# Conn_pcb4.net
KiCad netlist of a schematic drawn in EAGLE
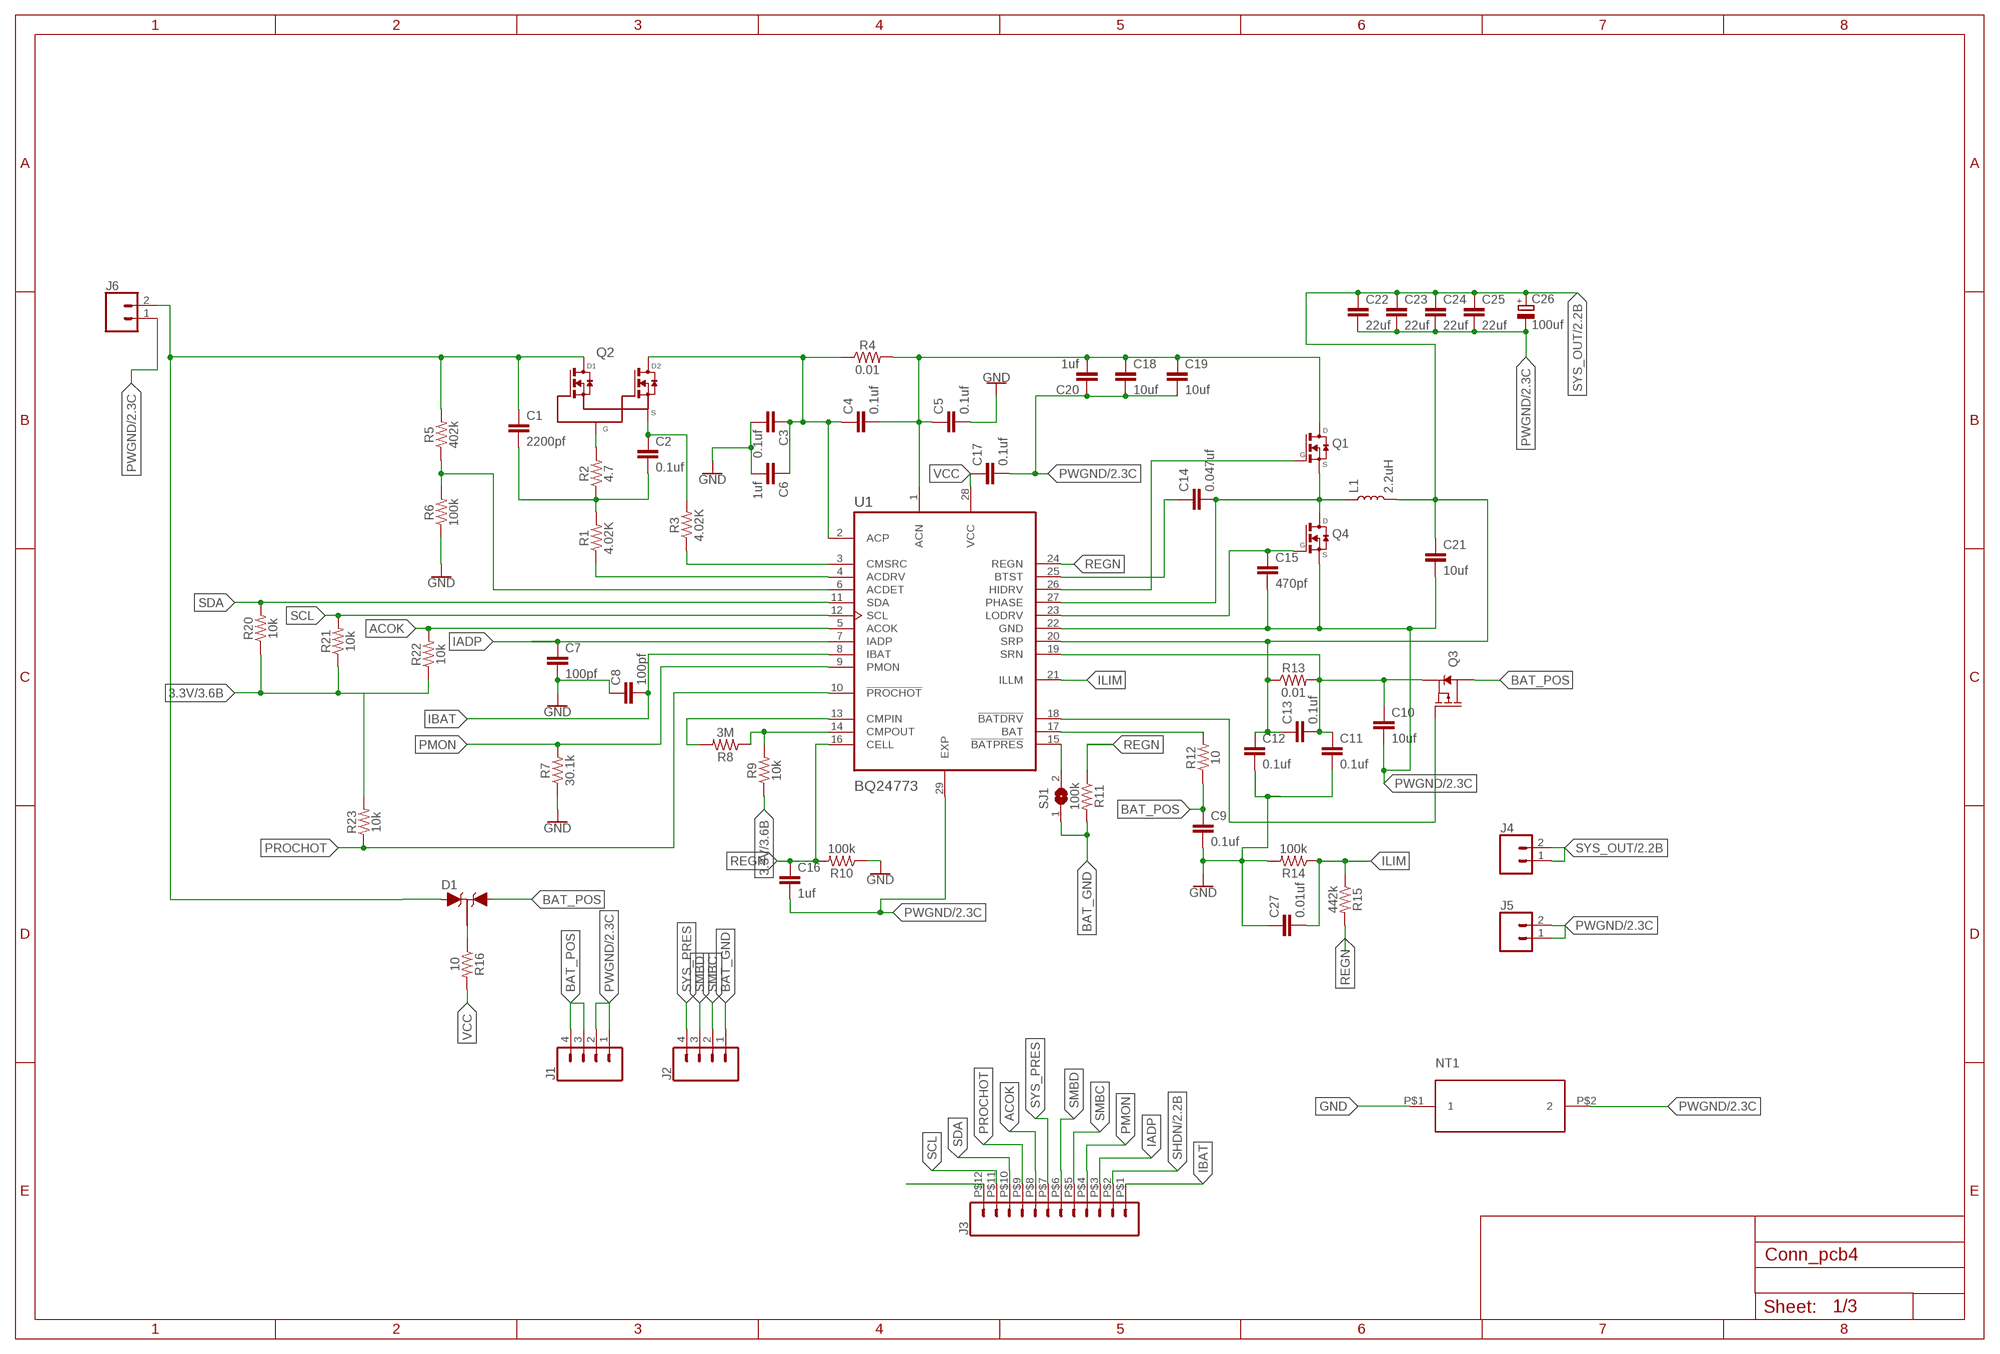
[diagram p0: schematic, sheet 1]
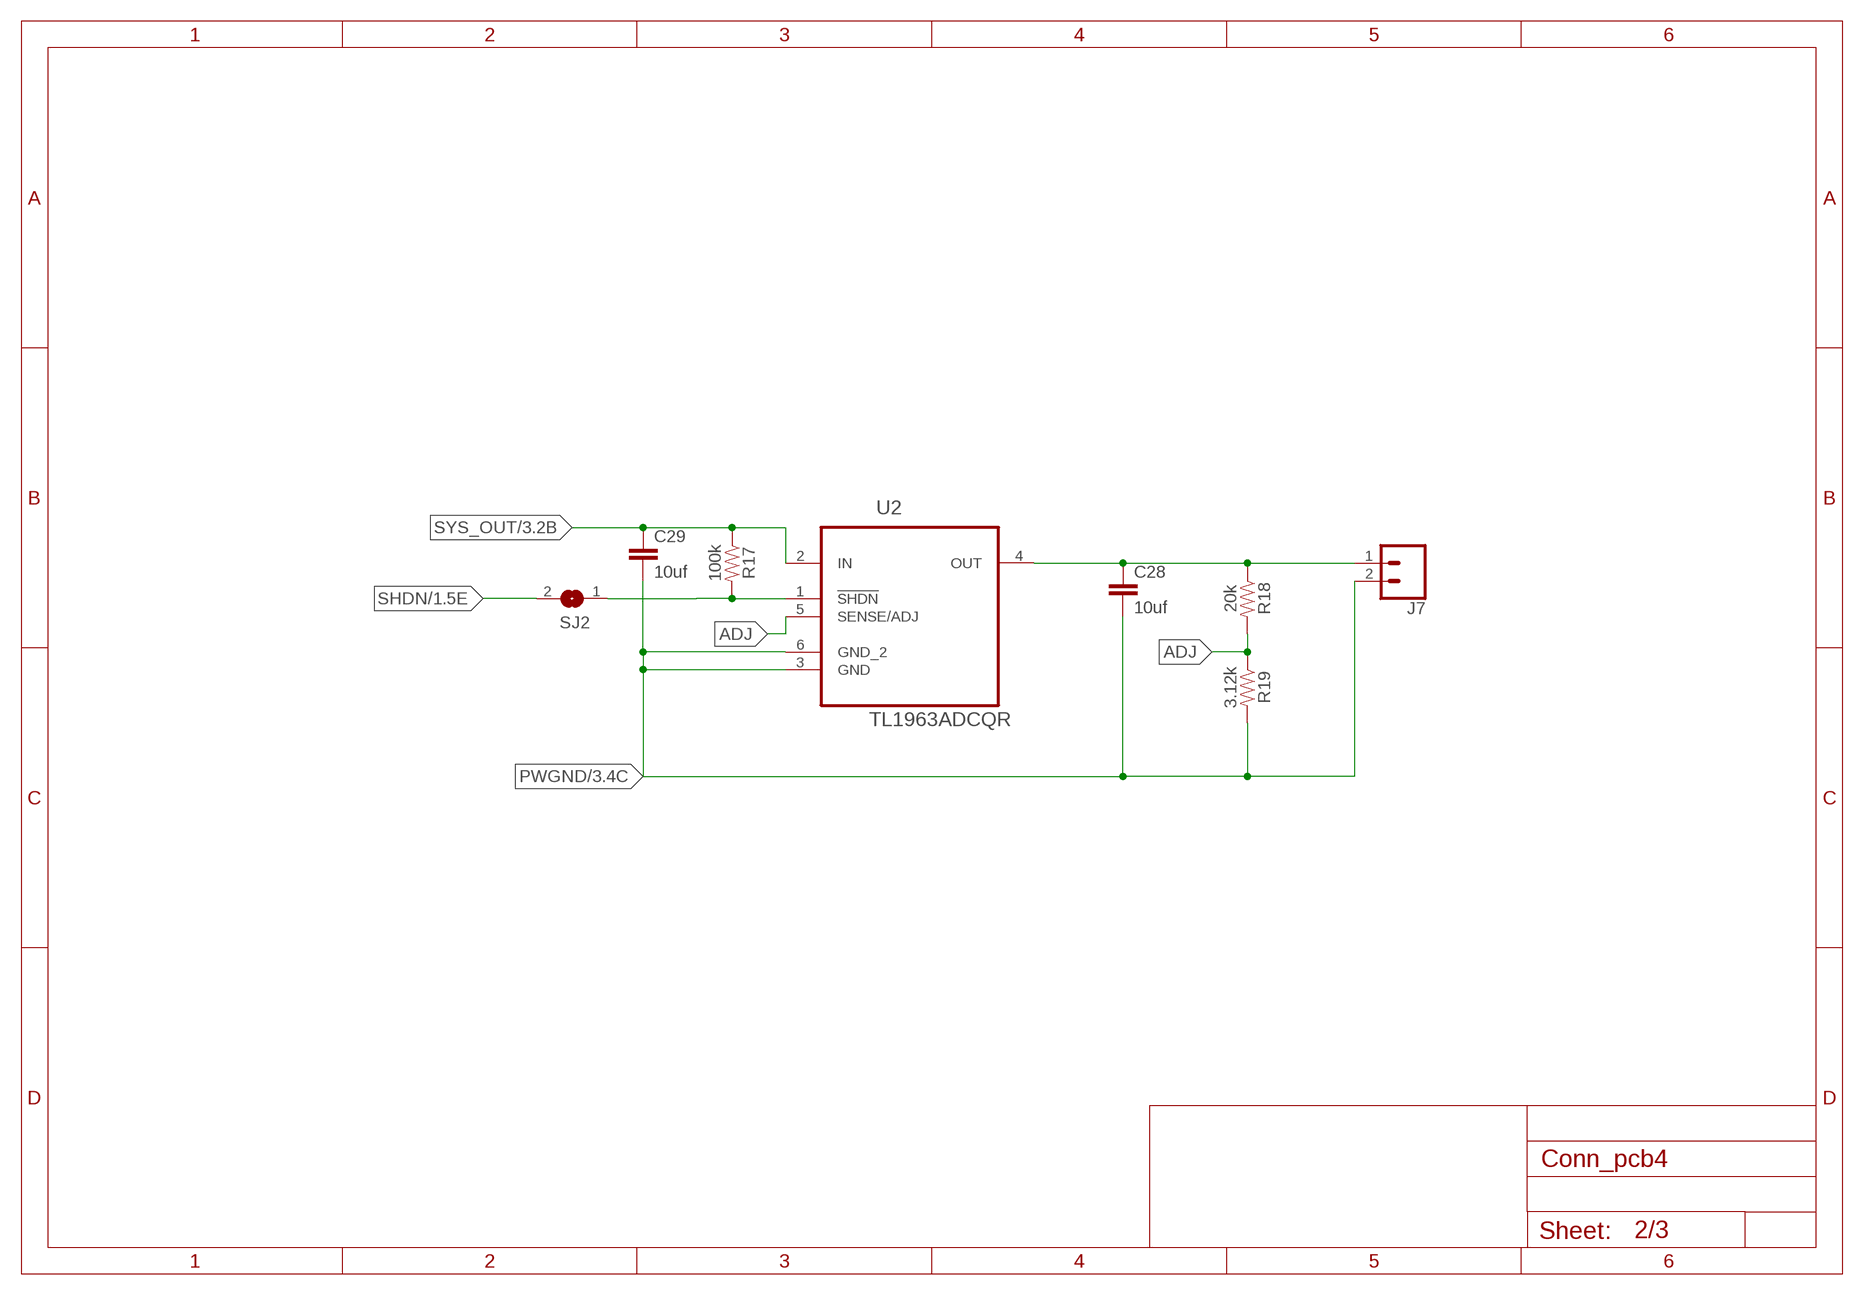
[diagram p1: schematic, sheet 2]
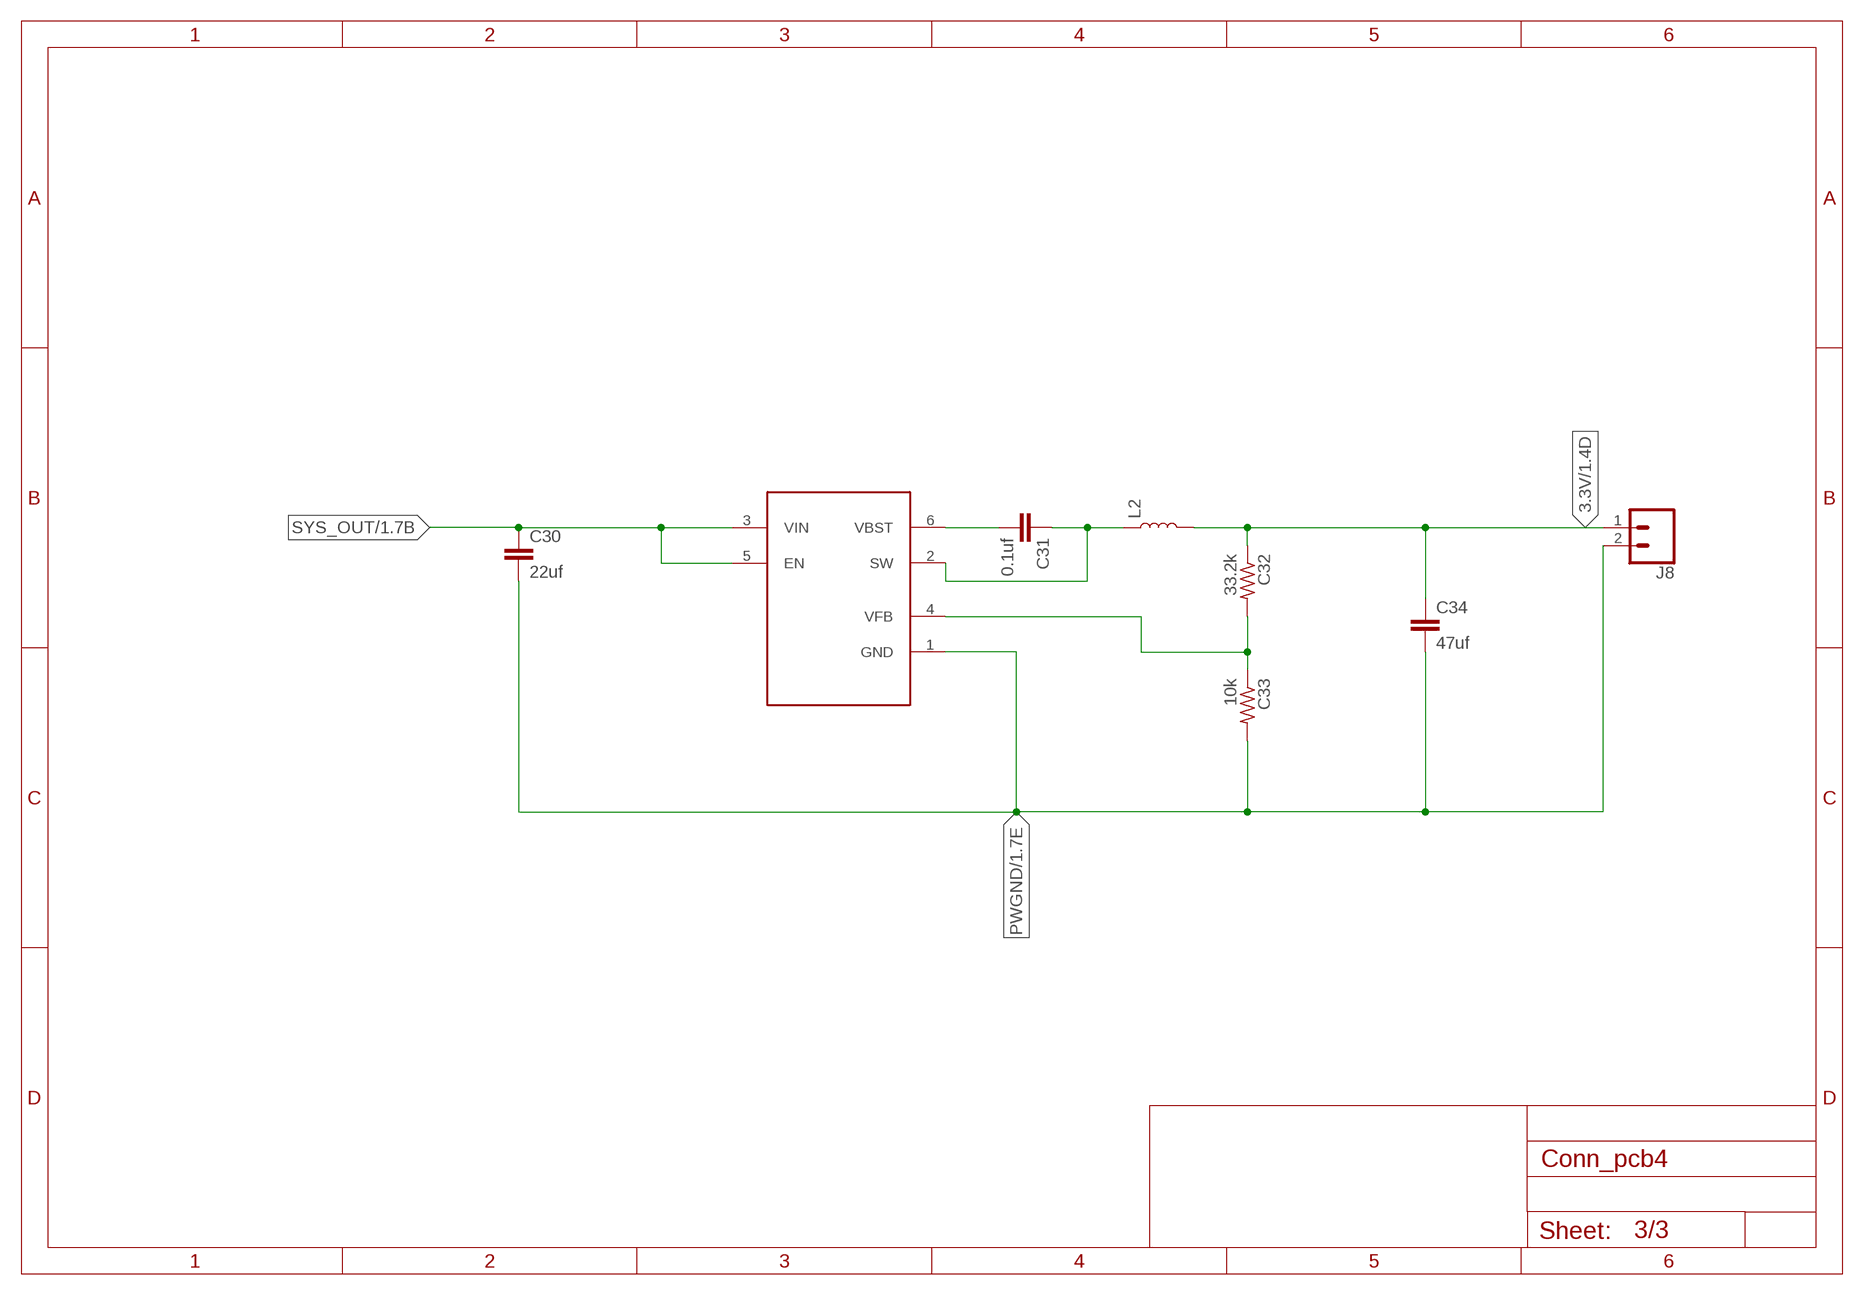
[diagram p2: schematic, sheet 3]

(export (version "E")
  (design (tool "Eeschema 10.0.6"))
  (components
    (comp (ref "C28")
      (value "10uf")
      (footprint "eagle-import:C0805K")
      (libsource (lib "eagle-import") (part "C-EUC0805K"))
    )
    (comp (ref "C29")
      (value "10uf")
      (footprint "eagle-import:C0805K")
      (libsource (lib "eagle-import") (part "C-EUC0805K"))
    )
    (comp (ref "J7")
      (value "CONN_02")
      (footprint "eagle-import:1X02")
      (libsource (lib "eagle-import") (part "CONN_02"))
    )
    (comp (ref "R17")
      (value "100k")
      (footprint "eagle-import:0402")
      (libsource (lib "eagle-import") (part "RES4K04020402"))
    )
    (comp (ref "R18")
      (value "20k")
      (footprint "eagle-import:0402")
      (libsource (lib "eagle-import") (part "RES4K04020402"))
    )
    (comp (ref "R19")
      (value "3.12k")
      (footprint "eagle-import:0402")
      (libsource (lib "eagle-import") (part "RES4K04020402"))
    )
    (comp (ref "SJ2") (value "SJ") (footprint "eagle-import:SJ") (libsource (lib "eagle-import") (part "SJ")))
    (comp (ref "U2")
      (value "TL1963ADCQR")
      (footprint "eagle-import:SOT127P706X180-6")
      (libsource (lib "eagle-import") (part "TL1963ADCQR"))
    )
    (comp (ref "C30")
      (value "22uf")
      (footprint "eagle-import:C1206")
      (libsource (lib "eagle-import") (part "C-EUC1206"))
    )
    (comp (ref "C31")
      (value "0.1uf")
      (footprint "eagle-import:CAPC1005X50")
      (libsource (lib "eagle-import") (part "CAP0402"))
    )
    (comp (ref "C32")
      (value "33.2k")
      (footprint "eagle-import:R0805")
      (libsource (lib "eagle-import") (part "R-US_R0805"))
    )
    (comp (ref "C33")
      (value "10k")
      (footprint "eagle-import:R0603")
      (libsource (lib "eagle-import") (part "R-US_R0603"))
    )
    (comp (ref "C34")
      (value "47uf")
      (footprint "eagle-import:C1206K")
      (libsource (lib "eagle-import") (part "C-EUC1206K"))
    )
    (comp (ref "J8")
      (value "CONN_02")
      (footprint "eagle-import:1X02")
      (libsource (lib "eagle-import") (part "CONN_02"))
    )
    (comp (ref "L2")
      (value "ASPI-4030S-3R3M-T")
      (footprint "eagle-import:INDDFN400X400X300-2")
      (libsource (lib "eagle-import") (part "ASPI-4030S-3R3M-T"))
    )
    (comp (ref "U3")
      (value "TPS561208DDCR")
      (footprint "eagle-import:SOT95P280X110-6")
      (libsource (lib "eagle-import") (part "TPS561208DDCR"))
    )
    (comp (ref "C1")
      (value "2200pf")
      (footprint "eagle-import:CAPC1005X50")
      (libsource (lib "eagle-import") (part "CAP0402"))
    )
    (comp (ref "C2")
      (value "0.1uf")
      (footprint "eagle-import:CAPC1005X50")
      (libsource (lib "eagle-import") (part "CAP0402"))
    )
    (comp (ref "C3")
      (value "0.1uf")
      (footprint "eagle-import:CAPC1005X50")
      (libsource (lib "eagle-import") (part "CAP0402"))
    )
    (comp (ref "C4")
      (value "0.1uf")
      (footprint "eagle-import:CAPC1005X50")
      (libsource (lib "eagle-import") (part "CAP0402"))
    )
    (comp (ref "C5")
      (value "0.1uf")
      (footprint "eagle-import:CAPC1005X50")
      (libsource (lib "eagle-import") (part "CAP0402"))
    )
    (comp (ref "C6")
      (value "1uf")
      (footprint "eagle-import:CAPC1005X50")
      (libsource (lib "eagle-import") (part "CAP0402"))
    )
    (comp (ref "C7")
      (value "100pf")
      (footprint "eagle-import:CAPC1005X50")
      (libsource (lib "eagle-import") (part "CAP0402"))
    )
    (comp (ref "C8")
      (value "100pf")
      (footprint "eagle-import:CAPC1005X50")
      (libsource (lib "eagle-import") (part "CAP0402"))
    )
    (comp (ref "C9")
      (value "0.1uf")
      (footprint "eagle-import:CAPC1005X50")
      (libsource (lib "eagle-import") (part "CAP0402"))
    )
    (comp (ref "C10")
      (value "10uf")
      (footprint "eagle-import:C0805K")
      (libsource (lib "eagle-import") (part "C-EUC0805K"))
    )
    (comp (ref "C11")
      (value "0.1uf")
      (footprint "eagle-import:CAPC1005X50")
      (libsource (lib "eagle-import") (part "CAP0402"))
    )
    (comp (ref "C12")
      (value "0.1uf")
      (footprint "eagle-import:CAPC1005X50")
      (libsource (lib "eagle-import") (part "CAP0402"))
    )
    (comp (ref "C13")
      (value "0.1uf")
      (footprint "eagle-import:CAPC1005X50")
      (libsource (lib "eagle-import") (part "CAP0402"))
    )
    (comp (ref "C14")
      (value "0.047uf")
      (footprint "eagle-import:CAPC1005X50")
      (libsource (lib "eagle-import") (part "CAP0402"))
    )
    (comp (ref "C15")
      (value "470pf")
      (footprint "eagle-import:CAPC1005X50")
      (libsource (lib "eagle-import") (part "CAP0402"))
    )
    (comp (ref "C16")
      (value "1uf")
      (footprint "eagle-import:CAPC1005X50")
      (libsource (lib "eagle-import") (part "CAP0402"))
    )
    (comp (ref "C17")
      (value "0.1uf")
      (footprint "eagle-import:CAPC1005X50")
      (libsource (lib "eagle-import") (part "CAP0402"))
    )
    (comp (ref "C18")
      (value "10uf")
      (footprint "eagle-import:C0805K")
      (libsource (lib "eagle-import") (part "C-EUC0805K"))
    )
    (comp (ref "C19")
      (value "10uf")
      (footprint "eagle-import:C0805K")
      (libsource (lib "eagle-import") (part "C-EUC0805K"))
    )
    (comp (ref "C20")
      (value "1uf")
      (footprint "eagle-import:CAPC1005X50")
      (libsource (lib "eagle-import") (part "CAP0402"))
    )
    (comp (ref "C21")
      (value "10uf")
      (footprint "eagle-import:C0805K")
      (libsource (lib "eagle-import") (part "C-EUC0805K"))
    )
    (comp (ref "C22")
      (value "22uf")
      (footprint "eagle-import:C1206")
      (libsource (lib "eagle-import") (part "C-EUC1206"))
    )
    (comp (ref "C23")
      (value "22uf")
      (footprint "eagle-import:C1206")
      (libsource (lib "eagle-import") (part "C-EUC1206"))
    )
    (comp (ref "C24")
      (value "22uf")
      (footprint "eagle-import:C1206")
      (libsource (lib "eagle-import") (part "C-EUC1206"))
    )
    (comp (ref "C25")
      (value "22uf")
      (footprint "eagle-import:C1206")
      (libsource (lib "eagle-import") (part "C-EUC1206"))
    )
    (comp (ref "C26")
      (value "100uf")
      (footprint "eagle-import:CAPAE1030X800")
      (libsource (lib "eagle-import") (part "16SVP100M"))
    )
    (comp (ref "C27")
      (value "0.01uf")
      (footprint "eagle-import:CAPC1005X50")
      (libsource (lib "eagle-import") (part "CAP0402"))
    )
    (comp (ref "D1")
      (value "BAT54C-7-F")
      (footprint "eagle-import:SOT95P235X110-3")
      (libsource (lib "eagle-import") (part "BAT54C-7-F"))
    )
    (comp (ref "J1")
      (value "CONN_041.3")
      (footprint "eagle-import:1X04_NO_SILK_1.3")
      (libsource (lib "eagle-import") (part "CONN_041.3"))
    )
    (comp (ref "J2")
      (value "CONN_041.3")
      (footprint "eagle-import:1X04_NO_SILK_1.3")
      (libsource (lib "eagle-import") (part "CONN_041.3"))
    )
    (comp (ref "J3")
      (value "62674-121121ALF")
      (footprint "eagle-import:62674-121121ALF")
      (libsource (lib "eagle-import") (part "62674-121121ALF"))
    )
    (comp (ref "J4")
      (value "CONN_021.4HOLE")
      (footprint "eagle-import:1X02_1.4HOLE")
      (libsource (lib "eagle-import") (part "CONN_021.4HOLE"))
    )
    (comp (ref "J5")
      (value "CONN_021.4HOLE")
      (footprint "eagle-import:1X02_1.4HOLE")
      (libsource (lib "eagle-import") (part "CONN_021.4HOLE"))
    )
    (comp (ref "J6")
      (value "CONN_021.4HOLE")
      (footprint "eagle-import:1X02_1.4HOLE")
      (libsource (lib "eagle-import") (part "CONN_021.4HOLE"))
    )
    (comp (ref "L1")
      (value "2.2uH")
      (footprint "eagle-import:RESM6365X610")
      (libsource (lib "eagle-import") (part "XEL6060-222MEB"))
    )
    (comp (ref "NT1")
      (value "NET_TIE")
      (footprint "eagle-import:NET_TIE")
      (libsource (lib "eagle-import") (part "NET_TIE"))
    )
    (comp (ref "Q1")
      (value "CSD17308Q3")
      (footprint "eagle-import:SON65P330X330X110-8")
      (fields (field (name "SPICEPREFIX") "Q"))
      (libsource (lib "eagle-import") (part "CSD17308Q3"))
    )
    (comp (ref "Q2")
      (value "CSD87312Q3EVSON")
      (footprint "eagle-import:QFN65P330X330X100-12")
      (libsource (lib "eagle-import") (part "CSD87312Q3EVSON"))
    )
    (comp (ref "Q3")
      (value "CSD25402Q3A")
      (footprint "eagle-import:CSD25402Q3A")
      (libsource (lib "eagle-import") (part "CSD25402Q3A"))
    )
    (comp (ref "Q4")
      (value "CSD17308Q3")
      (footprint "eagle-import:SON65P330X330X110-8")
      (fields (field (name "SPICEPREFIX") "Q"))
      (libsource (lib "eagle-import") (part "CSD17308Q3"))
    )
    (comp (ref "R1")
      (value "4.02K")
      (footprint "eagle-import:0402")
      (libsource (lib "eagle-import") (part "RES4K04020402"))
    )
    (comp (ref "R2")
      (value "4.7")
      (footprint "eagle-import:0402")
      (libsource (lib "eagle-import") (part "RES4K04020402"))
    )
    (comp (ref "R3")
      (value "4.02K")
      (footprint "eagle-import:0402")
      (libsource (lib "eagle-import") (part "RES4K04020402"))
    )
    (comp (ref "R4")
      (value "0.01")
      (footprint "eagle-import:1206")
      (libsource (lib "eagle-import") (part "SENSE-RES"))
    )
    (comp (ref "R5")
      (value "402k")
      (footprint "eagle-import:0402")
      (libsource (lib "eagle-import") (part "RES4K04020402"))
    )
    (comp (ref "R6")
      (value "100k")
      (footprint "eagle-import:0402")
      (libsource (lib "eagle-import") (part "RES4K04020402"))
    )
    (comp (ref "R7")
      (value "30.1k")
      (footprint "eagle-import:0402")
      (libsource (lib "eagle-import") (part "RES4K04020402"))
    )
    (comp (ref "R8")
      (value "3M")
      (footprint "eagle-import:0402")
      (libsource (lib "eagle-import") (part "RES4K04020402"))
    )
    (comp (ref "R9")
      (value "10k")
      (footprint "eagle-import:0402")
      (libsource (lib "eagle-import") (part "RES4K04020402"))
    )
    (comp (ref "R10")
      (value "100k")
      (footprint "eagle-import:0402")
      (libsource (lib "eagle-import") (part "RES4K04020402"))
    )
    (comp (ref "R11")
      (value "100k")
      (footprint "eagle-import:0402")
      (libsource (lib "eagle-import") (part "RES4K04020402"))
    )
    (comp (ref "R12")
      (value "10")
      (footprint "eagle-import:0402")
      (libsource (lib "eagle-import") (part "RES4K04020402"))
    )
    (comp (ref "R13")
      (value "0.01")
      (footprint "eagle-import:1206")
      (libsource (lib "eagle-import") (part "SENSE-RES"))
    )
    (comp (ref "R14")
      (value "100k")
      (footprint "eagle-import:0402")
      (libsource (lib "eagle-import") (part "RES4K04020402"))
    )
    (comp (ref "R15")
      (value "442k")
      (footprint "eagle-import:0402")
      (libsource (lib "eagle-import") (part "RES4K04020402"))
    )
    (comp (ref "R16")
      (value "10")
      (footprint "eagle-import:0402")
      (libsource (lib "eagle-import") (part "RES4K04020402"))
    )
    (comp (ref "R20")
      (value "10k")
      (footprint "eagle-import:0402")
      (libsource (lib "eagle-import") (part "RES4K04020402"))
    )
    (comp (ref "R21")
      (value "10k")
      (footprint "eagle-import:0402")
      (libsource (lib "eagle-import") (part "RES4K04020402"))
    )
    (comp (ref "R22")
      (value "10k")
      (footprint "eagle-import:0402")
      (libsource (lib "eagle-import") (part "RES4K04020402"))
    )
    (comp (ref "R23")
      (value "10k")
      (footprint "eagle-import:0402")
      (libsource (lib "eagle-import") (part "RES4K04020402"))
    )
    (comp (ref "SJ1") (value "SJ") (footprint "eagle-import:SJ") (libsource (lib "eagle-import") (part "SJ")))
    (comp (ref "U1")
      (value "BQ24773")
      (footprint "eagle-import:QFN40P400X400X80-29T240")
      (libsource (lib "eagle-import") (part "BQ24773"))
    )
  )
  (nets
    (net (code "1") (name "3.3V") (class "Default")
      (node (ref "C32") (pin "1") (pinfunction "1_1") (pintype "passive"))
      (node (ref "C34") (pin "1") (pinfunction "1_1") (pintype "passive"))
      (node (ref "J8") (pin "1") (pinfunction "1_1") (pintype "passive"))
      (node (ref "L2") (pin "2") (pinfunction "2_2") (pintype "passive"))
      (node (ref "R20") (pin "1") (pinfunction "1_1") (pintype "passive"))
      (node (ref "R21") (pin "1") (pinfunction "1_1") (pintype "passive"))
      (node (ref "R22") (pin "1") (pinfunction "1_1") (pintype "passive"))
      (node (ref "R23") (pin "2") (pinfunction "2_2") (pintype "passive"))
      (node (ref "R9") (pin "1") (pinfunction "1_1") (pintype "passive"))
    )
    (net (code "2") (name "ACOK") (class "Default")
      (node (ref "J3") (pin "P$8") (pinfunction "8_P$8") (pintype "passive"))
      (node (ref "R22") (pin "2") (pinfunction "2_2") (pintype "passive"))
      (node (ref "U1") (pin "5") (pinfunction "ACOK_5") (pintype "output"))
    )
    (net (code "3") (name "ADJ") (class "Default")
      (node (ref "R18") (pin "2") (pinfunction "2_2") (pintype "passive"))
      (node (ref "R19") (pin "1") (pinfunction "1_1") (pintype "passive"))
      (node (ref "U2") (pin "5") (pinfunction "SENSE/ADJ_5") (pintype "input"))
    )
    (net (code "4") (name "BAT_GND") (class "Default")
      (node (ref "J2") (pin "1") (pinfunction "1_1") (pintype "passive"))
      (node (ref "R11") (pin "2") (pinfunction "2_2") (pintype "passive"))
      (node (ref "SJ1") (pin "1") (pinfunction "1_1") (pintype "passive"))
    )
    (net (code "5") (name "BAT_POS") (class "Default")
      (node (ref "C9") (pin "1") (pinfunction "1_1") (pintype "passive"))
      (node (ref "D1") (pin "2") (pinfunction "A2_2") (pintype "passive"))
      (node (ref "J1") (pin "3") (pinfunction "3_3") (pintype "passive"))
      (node (ref "J1") (pin "4") (pinfunction "4_4") (pintype "passive"))
      (node (ref "Q3") (pin "1") (pinfunction "D_1") (pintype "bidirectional"))
      (node (ref "Q3") (pin "2") (pinfunction "D_2") (pintype "bidirectional"))
      (node (ref "Q3") (pin "3") (pinfunction "D_3") (pintype "bidirectional"))
      (node (ref "R12") (pin "1") (pinfunction "1_1") (pintype "passive"))
    )
    (net (code "6") (name "GND") (class "Default")
      (node (ref "C11") (pin "2") (pinfunction "2_2") (pintype "passive"))
      (node (ref "C12") (pin "2") (pinfunction "2_2") (pintype "passive"))
      (node (ref "C27") (pin "1") (pinfunction "1_1") (pintype "passive"))
      (node (ref "C3") (pin "2") (pinfunction "2_2") (pintype "passive"))
      (node (ref "C5") (pin "2") (pinfunction "2_2") (pintype "passive"))
      (node (ref "C6") (pin "2") (pinfunction "2_2") (pintype "passive"))
      (node (ref "C7") (pin "2") (pinfunction "2_2") (pintype "passive"))
      (node (ref "C8") (pin "1") (pinfunction "1_1") (pintype "passive"))
      (node (ref "C9") (pin "2") (pinfunction "2_2") (pintype "passive"))
      (node (ref "NT1") (pin "P$1") (pinfunction "1_P$1") (pintype "bidirectional"))
      (node (ref "R10") (pin "1") (pinfunction "1_1") (pintype "passive"))
      (node (ref "R14") (pin "2") (pinfunction "2_2") (pintype "passive"))
      (node (ref "R6") (pin "1") (pinfunction "1_1") (pintype "passive"))
      (node (ref "R7") (pin "1") (pinfunction "1_1") (pintype "passive"))
    )
    (net (code "7") (name "IADP") (class "Default")
      (node (ref "C7") (pin "1") (pinfunction "1_1") (pintype "passive"))
      (node (ref "J3") (pin "P$3") (pinfunction "3_P$3") (pintype "passive"))
      (node (ref "U1") (pin "7") (pinfunction "IADP_7") (pintype "output"))
    )
    (net (code "8") (name "IBAT") (class "Default")
      (node (ref "C8") (pin "2") (pinfunction "2_2") (pintype "passive"))
      (node (ref "J3") (pin "P$1") (pinfunction "1_P$1") (pintype "passive"))
      (node (ref "U1") (pin "8") (pinfunction "IBAT_8") (pintype "output"))
    )
    (net (code "9") (name "ILIM") (class "Default")
      (node (ref "C27") (pin "2") (pinfunction "2_2") (pintype "passive"))
      (node (ref "R14") (pin "1") (pinfunction "1_1") (pintype "passive"))
      (node (ref "R15") (pin "1") (pinfunction "1_1") (pintype "passive"))
      (node (ref "U1") (pin "21") (pinfunction "ILLM_21") (pintype "input"))
    )
    (net (code "10") (name "Net-(C1-Pad2)") (class "Default")
      (node (ref "C1") (pin "2") (pinfunction "2_2") (pintype "passive"))
      (node (ref "C2") (pin "2") (pinfunction "2_2") (pintype "passive"))
      (node (ref "R1") (pin "2") (pinfunction "2_2") (pintype "passive"))
      (node (ref "R2") (pin "1") (pinfunction "1_1") (pintype "passive"))
    )
    (net (code "11") (name "Net-(C2-Pad1)") (class "Default")
      (node (ref "C2") (pin "1") (pinfunction "1_1") (pintype "passive"))
      (node (ref "Q2") (pin "9") (pinfunction "S_9") (pintype "passive"))
      (node (ref "Q2") (pin "9.1") (pinfunction "S_9.1") (pintype "passive"))
      (node (ref "Q2") (pin "9.2") (pinfunction "S_9.2") (pintype "passive"))
      (node (ref "Q2") (pin "9.3") (pinfunction "S_9.3") (pintype "passive"))
      (node (ref "Q2") (pin "9.4") (pinfunction "S_9.4") (pintype "passive"))
      (node (ref "R3") (pin "2") (pinfunction "2_2") (pintype "passive"))
    )
    (net (code "12") (name "Net-(D1-A1)") (class "Default")
      (node (ref "C1") (pin "1") (pinfunction "1_1") (pintype "passive"))
      (node (ref "D1") (pin "1") (pinfunction "A1_1") (pintype "passive"))
      (node (ref "J6") (pin "2") (pinfunction "2_2") (pintype "passive"))
      (node (ref "Q2") (pin "1") (pinfunction "D1_1") (pintype "passive"))
      (node (ref "Q2") (pin "3") (pinfunction "D1_3") (pintype "passive"))
      (node (ref "Q2") (pin "4") (pinfunction "D1_4") (pintype "passive"))
      (node (ref "R5") (pin "2") (pinfunction "2_2") (pintype "passive"))
    )
    (net (code "13") (name "Net-(D1-K)") (class "Default")
      (node (ref "D1") (pin "3") (pinfunction "K_3") (pintype "passive"))
      (node (ref "R16") (pin "1") (pinfunction "1_1") (pintype "passive"))
    )
    (net (code "14") (name "Net-(Q1-G)") (class "Default")
      (node (ref "Q1") (pin "4") (pinfunction "G_4") (pintype "passive"))
      (node (ref "U1") (pin "26") (pinfunction "HIDRV_26") (pintype "output"))
    )
    (net (code "15") (name "Net-(Q2-G)") (class "Default")
      (node (ref "Q2") (pin "5") (pinfunction "G_5") (pintype "passive"))
      (node (ref "R2") (pin "2") (pinfunction "2_2") (pintype "passive"))
    )
    (net (code "16") (name "Net-(Q3-G)") (class "Default")
      (node (ref "Q3") (pin "4") (pinfunction "G_4") (pintype "bidirectional"))
      (node (ref "U1") (pin "18") (pinfunction "~{BATDRV}_18") (pintype "output"))
    )
    (net (code "17") (name "Net-(Q4-G)") (class "Default")
      (node (ref "C15") (pin "1") (pinfunction "1_1") (pintype "passive"))
      (node (ref "Q4") (pin "4") (pinfunction "G_4") (pintype "passive"))
      (node (ref "U1") (pin "23") (pinfunction "LODRV_23") (pintype "output"))
    )
    (net (code "18") (name "Net-(U1-ACDET)") (class "Default")
      (node (ref "R5") (pin "1") (pinfunction "1_1") (pintype "passive"))
      (node (ref "R6") (pin "2") (pinfunction "2_2") (pintype "passive"))
      (node (ref "U1") (pin "6") (pinfunction "ACDET_6") (pintype "input"))
    )
    (net (code "19") (name "Net-(U1-ACDRV)") (class "Default")
      (node (ref "R1") (pin "1") (pinfunction "1_1") (pintype "passive"))
      (node (ref "U1") (pin "4") (pinfunction "ACDRV_4") (pintype "output"))
    )
    (net (code "20") (name "Net-(U1-ACN)") (class "Default")
      (node (ref "C18") (pin "1") (pinfunction "1_1") (pintype "passive"))
      (node (ref "C19") (pin "1") (pinfunction "1_1") (pintype "passive"))
      (node (ref "C20") (pin "2") (pinfunction "2_2") (pintype "passive"))
      (node (ref "C4") (pin "2") (pinfunction "2_2") (pintype "passive"))
      (node (ref "C5") (pin "1") (pinfunction "1_1") (pintype "passive"))
      (node (ref "Q1") (pin "5") (pinfunction "D_5") (pintype "passive"))
      (node (ref "Q1") (pin "6") (pinfunction "D_6") (pintype "passive"))
      (node (ref "Q1") (pin "7") (pinfunction "D_7") (pintype "passive"))
      (node (ref "Q1") (pin "8") (pinfunction "D_8") (pintype "passive"))
      (node (ref "R4") (pin "2") (pinfunction "2_2") (pintype "passive"))
      (node (ref "U1") (pin "1") (pinfunction "ACN_1") (pintype "input"))
    )
    (net (code "21") (name "Net-(U1-ACP)") (class "Default")
      (node (ref "C3") (pin "1") (pinfunction "1_1") (pintype "passive"))
      (node (ref "C4") (pin "1") (pinfunction "1_1") (pintype "passive"))
      (node (ref "C6") (pin "1") (pinfunction "1_1") (pintype "passive"))
      (node (ref "Q2") (pin "6") (pinfunction "D2_6") (pintype "passive"))
      (node (ref "Q2") (pin "7") (pinfunction "D2_7") (pintype "passive"))
      (node (ref "Q2") (pin "8") (pinfunction "D2_8") (pintype "passive"))
      (node (ref "R4") (pin "1") (pinfunction "1_1") (pintype "passive"))
      (node (ref "U1") (pin "2") (pinfunction "ACP_2") (pintype "input"))
    )
    (net (code "22") (name "Net-(U1-BAT)") (class "Default")
      (node (ref "R12") (pin "2") (pinfunction "2_2") (pintype "passive"))
      (node (ref "U1") (pin "17") (pinfunction "BAT_17") (pintype "input"))
    )
    (net (code "23") (name "Net-(U1-BTST)") (class "Default")
      (node (ref "C14") (pin "1") (pinfunction "1_1") (pintype "passive"))
      (node (ref "U1") (pin "25") (pinfunction "BTST_25") (pintype "passive"))
    )
    (net (code "24") (name "Net-(U1-CMPIN)") (class "Default")
      (node (ref "R8") (pin "2") (pinfunction "2_2") (pintype "passive"))
      (node (ref "U1") (pin "13") (pinfunction "CMPIN_13") (pintype "input"))
    )
    (net (code "25") (name "Net-(U1-CMPOUT)") (class "Default")
      (node (ref "R8") (pin "1") (pinfunction "1_1") (pintype "passive"))
      (node (ref "R9") (pin "2") (pinfunction "2_2") (pintype "passive"))
      (node (ref "U1") (pin "14") (pinfunction "CMPOUT_14") (pintype "output"))
    )
    (net (code "26") (name "Net-(U1-CMSRC)") (class "Default")
      (node (ref "R3") (pin "1") (pinfunction "1_1") (pintype "passive"))
      (node (ref "U1") (pin "3") (pinfunction "CMSRC_3") (pintype "input"))
    )
    (net (code "27") (name "Net-(U1-PHASE)") (class "Default")
      (node (ref "C14") (pin "2") (pinfunction "2_2") (pintype "passive"))
      (node (ref "L1") (pin "1") (pinfunction "1_1") (pintype "passive"))
      (node (ref "Q1") (pin "1") (pinfunction "S_1") (pintype "passive"))
      (node (ref "Q1") (pin "2") (pinfunction "S_2") (pintype "passive"))
      (node (ref "Q1") (pin "3") (pinfunction "S_3") (pintype "passive"))
      (node (ref "Q4") (pin "5") (pinfunction "D_5") (pintype "passive"))
      (node (ref "Q4") (pin "6") (pinfunction "D_6") (pintype "passive"))
      (node (ref "Q4") (pin "7") (pinfunction "D_7") (pintype "passive"))
      (node (ref "Q4") (pin "8") (pinfunction "D_8") (pintype "passive"))
      (node (ref "U1") (pin "27") (pinfunction "PHASE_27") (pintype "output"))
    )
    (net (code "28") (name "Net-(U1-SRN)") (class "Default")
      (node (ref "C10") (pin "1") (pinfunction "1_1") (pintype "passive"))
      (node (ref "C11") (pin "1") (pinfunction "1_1") (pintype "passive"))
      (node (ref "C13") (pin "2") (pinfunction "2_2") (pintype "passive"))
      (node (ref "Q3") (pin "5") (pinfunction "S_5") (pintype "bidirectional"))
      (node (ref "Q3") (pin "6") (pinfunction "S_6") (pintype "bidirectional"))
      (node (ref "Q3") (pin "7") (pinfunction "S_7") (pintype "bidirectional"))
      (node (ref "Q3") (pin "8") (pinfunction "S_8") (pintype "bidirectional"))
      (node (ref "Q3") (pin "9") (pinfunction "S_9") (pintype "bidirectional"))
      (node (ref "R13") (pin "2") (pinfunction "2_2") (pintype "passive"))
      (node (ref "U1") (pin "19") (pinfunction "SRN_19") (pintype "input"))
    )
    (net (code "29") (name "Net-(U1-~{BATPRES})") (class "Default")
      (node (ref "SJ1") (pin "2") (pinfunction "2_2") (pintype "passive"))
      (node (ref "U1") (pin "15") (pinfunction "~{BATPRES}_15") (pintype "input"))
    )
    (net (code "30") (name "Net-(U2-OUT)") (class "Default")
      (node (ref "C28") (pin "1") (pinfunction "1_1") (pintype "passive"))
      (node (ref "J7") (pin "1") (pinfunction "1_1") (pintype "passive"))
      (node (ref "R18") (pin "1") (pinfunction "1_1") (pintype "passive"))
      (node (ref "U2") (pin "4") (pinfunction "OUT_4") (pintype "output"))
    )
    (net (code "31") (name "Net-(U2-~{SHDN})") (class "Default")
      (node (ref "R17") (pin "2") (pinfunction "2_2") (pintype "passive"))
      (node (ref "SJ2") (pin "1") (pinfunction "1_1") (pintype "passive"))
      (node (ref "U2") (pin "1") (pinfunction "~{SHDN}_1") (pintype "input"))
    )
    (net (code "32") (name "Net-(U3-SW)") (class "Default")
      (node (ref "C31") (pin "1") (pinfunction "1_1") (pintype "passive"))
      (node (ref "L2") (pin "1") (pinfunction "1_1") (pintype "passive"))
      (node (ref "U3") (pin "2") (pinfunction "SW_2") (pintype "bidirectional"))
    )
    (net (code "33") (name "Net-(U3-VBST)") (class "Default")
      (node (ref "C31") (pin "2") (pinfunction "2_2") (pintype "passive"))
      (node (ref "U3") (pin "6") (pinfunction "VBST_6") (pintype "bidirectional"))
    )
    (net (code "34") (name "Net-(U3-VFB)") (class "Default")
      (node (ref "C32") (pin "2") (pinfunction "2_2") (pintype "passive"))
      (node (ref "C33") (pin "1") (pinfunction "1_1") (pintype "passive"))
      (node (ref "U3") (pin "4") (pinfunction "VFB_4") (pintype "bidirectional"))
    )
    (net (code "35") (name "PMON") (class "Default")
      (node (ref "J3") (pin "P$4") (pinfunction "4_P$4") (pintype "passive"))
      (node (ref "R7") (pin "2") (pinfunction "2_2") (pintype "passive"))
      (node (ref "U1") (pin "9") (pinfunction "PMON_9") (pintype "output"))
    )
    (net (code "36") (name "PROCHOT") (class "Default")
      (node (ref "J3") (pin "P$9") (pinfunction "9_P$9") (pintype "passive"))
      (node (ref "R23") (pin "1") (pinfunction "1_1") (pintype "passive"))
      (node (ref "U1") (pin "10") (pinfunction "~{PROCHOT}_10") (pintype "output"))
    )
    (net (code "37") (name "PWGND") (class "Default")
      (node (ref "C10") (pin "2") (pinfunction "2_2") (pintype "passive"))
      (node (ref "C15") (pin "2") (pinfunction "2_2") (pintype "passive"))
      (node (ref "C16") (pin "2") (pinfunction "2_2") (pintype "passive"))
      (node (ref "C17") (pin "2") (pinfunction "2_2") (pintype "passive"))
      (node (ref "C18") (pin "2") (pinfunction "2_2") (pintype "passive"))
      (node (ref "C19") (pin "2") (pinfunction "2_2") (pintype "passive"))
      (node (ref "C20") (pin "1") (pinfunction "1_1") (pintype "passive"))
      (node (ref "C21") (pin "2") (pinfunction "2_2") (pintype "passive"))
      (node (ref "C22") (pin "2") (pinfunction "2_2") (pintype "passive"))
      (node (ref "C23") (pin "2") (pinfunction "2_2") (pintype "passive"))
      (node (ref "C24") (pin "2") (pinfunction "2_2") (pintype "passive"))
      (node (ref "C25") (pin "2") (pinfunction "2_2") (pintype "passive"))
      (node (ref "C26") (pin "2") (pinfunction "-_2") (pintype "passive"))
      (node (ref "C28") (pin "2") (pinfunction "2_2") (pintype "passive"))
      (node (ref "C29") (pin "2") (pinfunction "2_2") (pintype "passive"))
      (node (ref "C30") (pin "2") (pinfunction "2_2") (pintype "passive"))
      (node (ref "C33") (pin "2") (pinfunction "2_2") (pintype "passive"))
      (node (ref "C34") (pin "2") (pinfunction "2_2") (pintype "passive"))
      (node (ref "J1") (pin "1") (pinfunction "1_1") (pintype "passive"))
      (node (ref "J1") (pin "2") (pinfunction "2_2") (pintype "passive"))
      (node (ref "J5") (pin "1") (pinfunction "1_1") (pintype "passive"))
      (node (ref "J5") (pin "2") (pinfunction "2_2") (pintype "passive"))
      (node (ref "J6") (pin "1") (pinfunction "1_1") (pintype "passive"))
      (node (ref "J7") (pin "2") (pinfunction "2_2") (pintype "passive"))
      (node (ref "J8") (pin "2") (pinfunction "2_2") (pintype "passive"))
      (node (ref "NT1") (pin "P$2") (pinfunction "2_P$2") (pintype "bidirectional"))
      (node (ref "Q4") (pin "1") (pinfunction "S_1") (pintype "passive"))
      (node (ref "Q4") (pin "2") (pinfunction "S_2") (pintype "passive"))
      (node (ref "Q4") (pin "3") (pinfunction "S_3") (pintype "passive"))
      (node (ref "R19") (pin "2") (pinfunction "2_2") (pintype "passive"))
      (node (ref "U1") (pin "22") (pinfunction "GND_22") (pintype "power_in"))
      (node (ref "U1") (pin "29") (pinfunction "EXP_29") (pintype "power_in"))
      (node (ref "U2") (pin "3") (pinfunction "GND_3") (pintype "passive"))
      (node (ref "U2") (pin "6") (pinfunction "GND_2_6") (pintype "input"))
      (node (ref "U3") (pin "1") (pinfunction "GND_1") (pintype "bidirectional"))
    )
    (net (code "38") (name "REGN") (class "Default")
      (node (ref "C16") (pin "1") (pinfunction "1_1") (pintype "passive"))
      (node (ref "R10") (pin "2") (pinfunction "2_2") (pintype "passive"))
      (node (ref "R11") (pin "1") (pinfunction "1_1") (pintype "passive"))
      (node (ref "R15") (pin "2") (pinfunction "2_2") (pintype "passive"))
      (node (ref "U1") (pin "16") (pinfunction "CELL_16") (pintype "input"))
      (node (ref "U1") (pin "24") (pinfunction "REGN_24") (pintype "output"))
    )
    (net (code "39") (name "SCL") (class "Default")
      (node (ref "J3") (pin "P$11") (pinfunction "11_P$11") (pintype "passive"))
      (node (ref "R21") (pin "2") (pinfunction "2_2") (pintype "passive"))
      (node (ref "U1") (pin "12") (pinfunction "SCL_12") (pintype "input"))
    )
    (net (code "40") (name "SDA") (class "Default")
      (node (ref "J3") (pin "P$10") (pinfunction "10_P$10") (pintype "passive"))
      (node (ref "R20") (pin "2") (pinfunction "2_2") (pintype "passive"))
      (node (ref "U1") (pin "11") (pinfunction "SDA_11") (pintype "bidirectional"))
    )
    (net (code "41") (name "SHDN") (class "Default")
      (node (ref "J3") (pin "P$2") (pinfunction "2_P$2") (pintype "passive"))
      (node (ref "SJ2") (pin "2") (pinfunction "2_2") (pintype "passive"))
    )
    (net (code "42") (name "SMBC") (class "Default")
      (node (ref "J2") (pin "2") (pinfunction "2_2") (pintype "passive"))
      (node (ref "J3") (pin "P$5") (pinfunction "5_P$5") (pintype "passive"))
    )
    (net (code "43") (name "SMBD") (class "Default")
      (node (ref "J2") (pin "3") (pinfunction "3_3") (pintype "passive"))
      (node (ref "J3") (pin "P$6") (pinfunction "6_P$6") (pintype "passive"))
    )
    (net (code "44") (name "SYS_OUT") (class "Default")
      (node (ref "C12") (pin "1") (pinfunction "1_1") (pintype "passive"))
      (node (ref "C13") (pin "1") (pinfunction "1_1") (pintype "passive"))
      (node (ref "C21") (pin "1") (pinfunction "1_1") (pintype "passive"))
      (node (ref "C22") (pin "1") (pinfunction "1_1") (pintype "passive"))
      (node (ref "C23") (pin "1") (pinfunction "1_1") (pintype "passive"))
      (node (ref "C24") (pin "1") (pinfunction "1_1") (pintype "passive"))
      (node (ref "C25") (pin "1") (pinfunction "1_1") (pintype "passive"))
      (node (ref "C26") (pin "1") (pinfunction "+_1") (pintype "passive"))
      (node (ref "C29") (pin "1") (pinfunction "1_1") (pintype "passive"))
      (node (ref "C30") (pin "1") (pinfunction "1_1") (pintype "passive"))
      (node (ref "J4") (pin "1") (pinfunction "1_1") (pintype "passive"))
      (node (ref "J4") (pin "2") (pinfunction "2_2") (pintype "passive"))
      (node (ref "L1") (pin "2") (pinfunction "2_2") (pintype "passive"))
      (node (ref "R13") (pin "1") (pinfunction "1_1") (pintype "passive"))
      (node (ref "R17") (pin "1") (pinfunction "1_1") (pintype "passive"))
      (node (ref "U1") (pin "20") (pinfunction "SRP_20") (pintype "input"))
      (node (ref "U2") (pin "2") (pinfunction "IN_2") (pintype "input"))
      (node (ref "U3") (pin "3") (pinfunction "VIN_3") (pintype "bidirectional"))
      (node (ref "U3") (pin "5") (pinfunction "EN_5") (pintype "bidirectional"))
    )
    (net (code "45") (name "SYS_PRES") (class "Default")
      (node (ref "J2") (pin "4") (pinfunction "4_4") (pintype "passive"))
      (node (ref "J3") (pin "P$7") (pinfunction "7_P$7") (pintype "passive"))
    )
    (net (code "46") (name "VCC") (class "Default")
      (node (ref "C17") (pin "1") (pinfunction "1_1") (pintype "passive"))
      (node (ref "R16") (pin "2") (pinfunction "2_2") (pintype "passive"))
      (node (ref "U1") (pin "28") (pinfunction "VCC_28") (pintype "power_in"))
    )
    (net (code "47") (name "unconnected-(J3-12-PadP$12)") (class "Default")
      (node (ref "J3") (pin "P$12") (pinfunction "12_P$12") (pintype "passive"))
    )
  )
)
